# coqui-v1_0.net
KiCad netlist of a schematic drawn in EAGLE
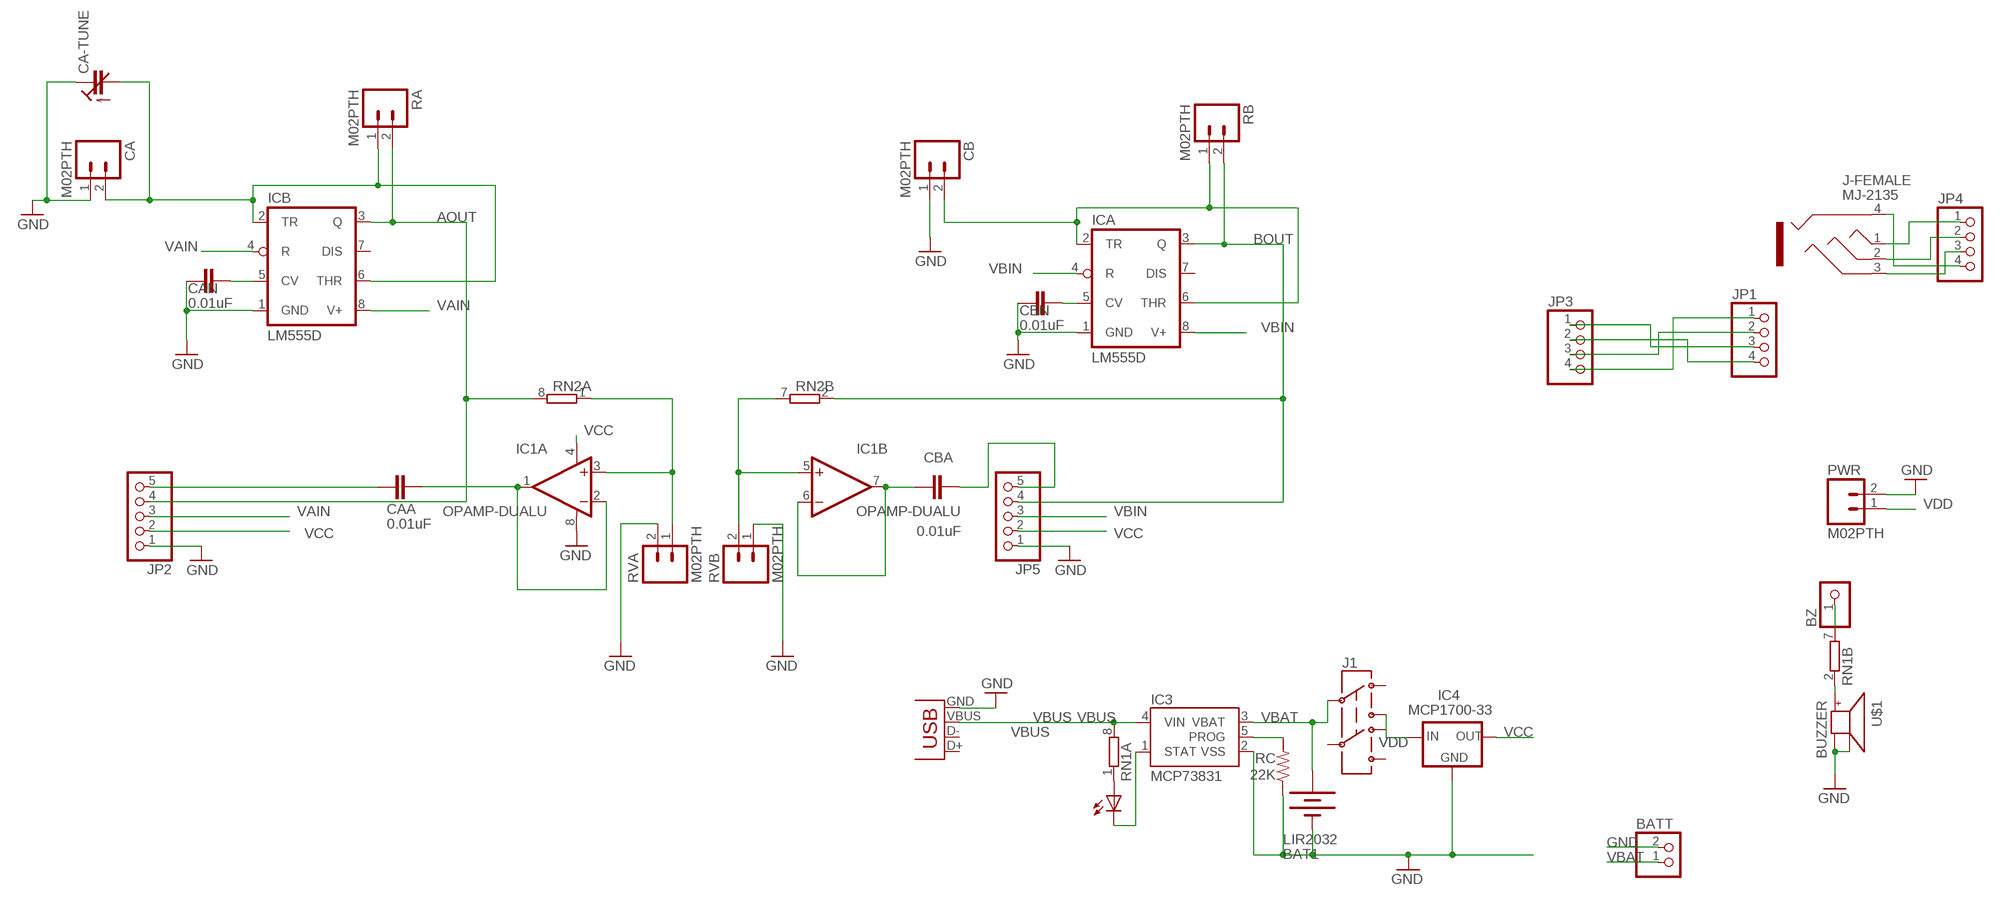
[diagram p0: schematic, sheet 1]

(export (version "E")
  (design (tool "Eeschema 10.0.6"))
  (components
    (comp (ref "BAT1")
      (value "LIR2032")
      (footprint "eagle-import:BATTCOM_20MM_PTH_SMT")
      (libsource (lib "eagle-import") (part "BATTERYBATTCOM_20MM_PTH_SMT"))
    )
    (comp (ref "BATT")
      (value "JST_2PIN-SMT-RA")
      (footprint "eagle-import:JST-PH-2-SMT-RA")
      (libsource (lib "eagle-import") (part "JST_2PIN-SMT-RA"))
    )
    (comp (ref "BZ")
      (value "PINHD-1X1")
      (footprint "eagle-import:1X01")
      (libsource (lib "eagle-import") (part "PINHD-1X1"))
    )
    (comp (ref "CA")
      (value "M02PTH")
      (footprint "eagle-import:1X02")
      (libsource (lib "eagle-import") (part "M02PTH"))
    )
    (comp (ref "CA-TUNE")
      (value "C-TRIMMTZBX4")
      (footprint "eagle-import:CTRIMTZBX4")
      (libsource (lib "eagle-import") (part "C-TRIMMTZBX4"))
    )
    (comp (ref "CAA")
      (value "0.01uF")
      (footprint "eagle-import:C0805@1")
      (libsource (lib "eagle-import") (part "C-EUC0805"))
    )
    (comp (ref "CAN")
      (value "0.01uF")
      (footprint "eagle-import:C0805@1")
      (libsource (lib "eagle-import") (part "C-EUC0805"))
    )
    (comp (ref "CB")
      (value "M02PTH")
      (footprint "eagle-import:1X02")
      (libsource (lib "eagle-import") (part "M02PTH"))
    )
    (comp (ref "CBA")
      (value "0.01uF")
      (footprint "eagle-import:C0805@1")
      (libsource (lib "eagle-import") (part "C-EUC0805"))
    )
    (comp (ref "CBN")
      (value "0.01uF")
      (footprint "eagle-import:C0805@1")
      (libsource (lib "eagle-import") (part "C-EUC0805"))
    )
    (comp (ref "CHG")
      (value "0805")
      (footprint "eagle-import:CHIPLED_0805")
      (libsource (lib "eagle-import") (part "LEDCHIPLED_0805"))
    )
    (comp (ref "IC1")
      (value "OPAMP-DUALU")
      (footprint "eagle-import:SO08")
      (libsource (lib "eagle-import") (part "OPAMP-DUALU"))
    )
    (comp (ref "IC3")
      (value "MCP73831")
      (footprint "eagle-import:SOT23-5")
      (libsource (lib "eagle-import") (part "MCP73831"))
    )
    (comp (ref "IC4")
      (value "MCP1700-33")
      (footprint "eagle-import:SOT89")
      (libsource (lib "eagle-import") (part "MCP1700SOT89"))
    )
    (comp (ref "ICA")
      (value "LM555D")
      (footprint "eagle-import:SO08")
      (libsource (lib "eagle-import") (part "555DLM"))
    )
    (comp (ref "ICB")
      (value "LM555D")
      (footprint "eagle-import:SO08")
      (libsource (lib "eagle-import") (part "555DLM"))
    )
    (comp (ref "J-FEMALE")
      (value "MJ-2135")
      (footprint "eagle-import:MJ-2135")
      (libsource (lib "eagle-import") (part "MJ-2135"))
    )
    (comp (ref "J1")
      (value "AYZ0202")
      (footprint "eagle-import:AYZ0202")
      (libsource (lib "eagle-import") (part "AYZ0202"))
    )
    (comp (ref "JP1")
      (value "PINHD-1X4/90")
      (footprint "eagle-import:1X04_90")
      (libsource (lib "eagle-import") (part "trrs-dwb_PINHD-1X4/90"))
    )
    (comp (ref "JP2")
      (value "PINHD-1X5")
      (footprint "eagle-import:1X05")
      (libsource (lib "eagle-import") (part "PINHD-1X5"))
    )
    (comp (ref "JP3")
      (value "PINHD-1X4")
      (footprint "eagle-import:1X04")
      (libsource (lib "eagle-import") (part "PINHD-1X4"))
    )
    (comp (ref "JP4")
      (value "PINHD-1X4")
      (footprint "eagle-import:1X04")
      (libsource (lib "eagle-import") (part "PINHD-1X4"))
    )
    (comp (ref "JP5")
      (value "PINHD-1X5")
      (footprint "eagle-import:1X05")
      (libsource (lib "eagle-import") (part "PINHD-1X5"))
    )
    (comp (ref "PWR")
      (value "M02PTH")
      (footprint "eagle-import:1X02")
      (libsource (lib "eagle-import") (part "M02PTH"))
    )
    (comp (ref "RA")
      (value "M02PTH")
      (footprint "eagle-import:1X02")
      (libsource (lib "eagle-import") (part "M02PTH"))
    )
    (comp (ref "RB")
      (value "M02PTH")
      (footprint "eagle-import:1X02")
      (libsource (lib "eagle-import") (part "M02PTH"))
    )
    (comp (ref "RC")
      (value "22K")
      (footprint "eagle-import:R0805")
      (libsource (lib "eagle-import") (part "R-US_R0805"))
    )
    (comp (ref "RN1")
      (value "4R-NEXB38V")
      (footprint "eagle-import:EXB38V")
      (libsource (lib "eagle-import") (part "4R-NEXB38V"))
    )
    (comp (ref "RN2")
      (value "4R-NEXB38V")
      (footprint "eagle-import:EXB38V")
      (libsource (lib "eagle-import") (part "4R-NEXB38V"))
    )
    (comp (ref "RVA")
      (value "M02PTH")
      (footprint "eagle-import:1X02")
      (libsource (lib "eagle-import") (part "M02PTH"))
    )
    (comp (ref "RVB")
      (value "M02PTH")
      (footprint "eagle-import:1X02")
      (libsource (lib "eagle-import") (part "M02PTH"))
    )
    (comp (ref "U$1")
      (value "BUZZER")
      (footprint "eagle-import:SMT-8585-BUZZER")
      (libsource (lib "eagle-import") (part "BUZZER"))
    )
    (comp (ref "X1")
      (value "USBSMD")
      (footprint "eagle-import:USB-MINIB")
      (libsource (lib "eagle-import") (part "USBSMD"))
    )
  )
  (nets
    (net (code "1") (name "/AOUT") (class "Default")
      (node (ref "ICB") (pin "3") (pinfunction "Q_3") (pintype "output"))
      (node (ref "JP2") (pin "4") (pinfunction "4_4") (pintype "passive"))
      (node (ref "RA") (pin "2") (pinfunction "2_2") (pintype "passive"))
      (node (ref "RN2") (pin "8") (pinfunction "2_8") (pintype "passive"))
    )
    (net (code "2") (name "/BOUT") (class "Default")
      (node (ref "ICA") (pin "3") (pinfunction "Q_3") (pintype "output"))
      (node (ref "JP5") (pin "4") (pinfunction "4_4") (pintype "passive"))
      (node (ref "RB") (pin "2") (pinfunction "2_2") (pintype "passive"))
      (node (ref "RN2") (pin "2") (pinfunction "1_2") (pintype "passive"))
    )
    (net (code "3") (name "/N$23") (class "Default")
      (node (ref "IC1") (pin "3") (pinfunction "+IN_3") (pintype "input"))
      (node (ref "IC1") (pin "5") (pinfunction "+IN_5") (pintype "input"))
      (node (ref "RN2") (pin "1") (pinfunction "1_1") (pintype "passive"))
      (node (ref "RN2") (pin "7") (pinfunction "2_7") (pintype "passive"))
      (node (ref "RVA") (pin "1") (pinfunction "1_1") (pintype "passive"))
      (node (ref "RVB") (pin "2") (pinfunction "2_2") (pintype "passive"))
    )
    (net (code "4") (name "/VAIN") (class "Default")
      (node (ref "ICB") (pin "4") (pinfunction "R_4") (pintype "input"))
      (node (ref "ICB") (pin "8") (pinfunction "V+_8") (pintype "power_in"))
      (node (ref "JP2") (pin "3") (pinfunction "3_3") (pintype "passive"))
    )
    (net (code "5") (name "/VBAT") (class "Default")
      (node (ref "BAT1") (pin "P$2") (pinfunction "+_P$2") (pintype "power_in"))
      (node (ref "BATT") (pin "1") (pinfunction "2_1") (pintype "passive"))
      (node (ref "IC3") (pin "3") (pinfunction "VBAT_3") (pintype "power_in"))
      (node (ref "J1") (pin "2") (pinfunction "2_2") (pintype "bidirectional"))
    )
    (net (code "6") (name "/VBIN") (class "Default")
      (node (ref "ICA") (pin "4") (pinfunction "R_4") (pintype "input"))
      (node (ref "ICA") (pin "8") (pinfunction "V+_8") (pintype "power_in"))
      (node (ref "JP5") (pin "3") (pinfunction "3_3") (pintype "passive"))
    )
    (net (code "7") (name "/VBUS") (class "Default")
      (node (ref "IC3") (pin "4") (pinfunction "VIN_4") (pintype "power_in"))
      (node (ref "RN1") (pin "8") (pinfunction "2_8") (pintype "passive"))
      (node (ref "X1") (pin "VBUS") (pinfunction "VBUS_VBUS") (pintype "bidirectional"))
    )
    (net (code "8") (name "/VCC") (class "Default")
      (node (ref "IC1") (pin "4") (pinfunction "V-_4") (pintype "power_in"))
      (node (ref "IC4") (pin "3") (pinfunction "OUT_3") (pintype "passive"))
      (node (ref "JP2") (pin "2") (pinfunction "2_2") (pintype "passive"))
      (node (ref "JP5") (pin "2") (pinfunction "2_2") (pintype "passive"))
    )
    (net (code "9") (name "/VDD") (class "Default")
      (node (ref "IC4") (pin "2") (pinfunction "IN_2") (pintype "input"))
      (node (ref "J1") (pin "1") (pinfunction "3_1") (pintype "bidirectional"))
      (node (ref "PWR") (pin "1") (pinfunction "1_1") (pintype "passive"))
    )
    (net (code "10") (name "GND") (class "Default")
      (node (ref "BAT1") (pin "P$1") (pinfunction "-_P$1") (pintype "power_in"))
      (node (ref "BATT") (pin "2") (pinfunction "1_2") (pintype "passive"))
      (node (ref "CA") (pin "1") (pinfunction "1_1") (pintype "passive"))
      (node (ref "CA-TUNE") (pin "1") (pinfunction "E_1") (pintype "passive"))
      (node (ref "CAN") (pin "1") (pinfunction "1_1") (pintype "passive"))
      (node (ref "CB") (pin "1") (pinfunction "1_1") (pintype "passive"))
      (node (ref "CBN") (pin "1") (pinfunction "1_1") (pintype "passive"))
      (node (ref "IC1") (pin "8") (pinfunction "V+_8") (pintype "power_in"))
      (node (ref "IC3") (pin "2") (pinfunction "VSS_2") (pintype "power_in"))
      (node (ref "IC4") (pin "1") (pinfunction "GND_1") (pintype "input"))
      (node (ref "ICA") (pin "1") (pinfunction "GND_1") (pintype "power_in"))
      (node (ref "ICB") (pin "1") (pinfunction "GND_1") (pintype "power_in"))
      (node (ref "JP2") (pin "1") (pinfunction "1_1") (pintype "passive"))
      (node (ref "JP5") (pin "1") (pinfunction "1_1") (pintype "passive"))
      (node (ref "PWR") (pin "2") (pinfunction "2_2") (pintype "passive"))
      (node (ref "RC") (pin "1") (pinfunction "1_1") (pintype "passive"))
      (node (ref "RVA") (pin "2") (pinfunction "2_2") (pintype "passive"))
      (node (ref "RVB") (pin "1") (pinfunction "1_1") (pintype "passive"))
      (node (ref "U$1") (pin "-") (pinfunction "-_-") (pintype "passive"))
      (node (ref "U$1") (pin "A-") (pinfunction "A-_A-") (pintype "passive"))
      (node (ref "X1") (pin "GND") (pinfunction "GND_GND") (pintype "bidirectional"))
    )
    (net (code "11") (name "Net-(CA-TUNE-A)") (class "Default")
      (node (ref "CA") (pin "2") (pinfunction "2_2") (pintype "passive"))
      (node (ref "CA-TUNE") (pin "2") (pinfunction "A_2") (pintype "passive"))
      (node (ref "ICB") (pin "2") (pinfunction "TR_2") (pintype "input"))
      (node (ref "ICB") (pin "6") (pinfunction "THR_6") (pintype "input"))
      (node (ref "RA") (pin "1") (pinfunction "1_1") (pintype "passive"))
    )
    (net (code "12") (name "Net-(CAA-Pad1)") (class "Default")
      (node (ref "CAA") (pin "1") (pinfunction "1_1") (pintype "passive"))
      (node (ref "JP2") (pin "5") (pinfunction "5_5") (pintype "passive"))
    )
    (net (code "13") (name "Net-(CBA-Pad2)") (class "Default")
      (node (ref "CBA") (pin "2") (pinfunction "2_2") (pintype "passive"))
      (node (ref "JP5") (pin "5") (pinfunction "5_5") (pintype "passive"))
    )
    (net (code "14") (name "Net-(CHG-PadA)") (class "Default")
      (node (ref "CHG") (pin "A") (pinfunction "A_A") (pintype "passive"))
      (node (ref "RN1") (pin "1") (pinfunction "1_1") (pintype "passive"))
    )
    (net (code "15") (name "Net-(IC1A--IN)") (class "Default")
      (node (ref "CAA") (pin "2") (pinfunction "2_2") (pintype "passive"))
      (node (ref "IC1") (pin "1") (pinfunction "OUT_1") (pintype "output"))
      (node (ref "IC1") (pin "2") (pinfunction "-IN_2") (pintype "input"))
    )
    (net (code "16") (name "Net-(IC1B--IN)") (class "Default")
      (node (ref "CBA") (pin "1") (pinfunction "1_1") (pintype "passive"))
      (node (ref "IC1") (pin "6") (pinfunction "-IN_6") (pintype "input"))
      (node (ref "IC1") (pin "7") (pinfunction "OUT_7") (pintype "output"))
    )
    (net (code "17") (name "Net-(IC3-PROG)") (class "Default")
      (node (ref "IC3") (pin "5") (pinfunction "PROG_5") (pintype "input"))
      (node (ref "RC") (pin "2") (pinfunction "2_2") (pintype "passive"))
    )
    (net (code "18") (name "Net-(IC3-STAT)") (class "Default")
      (node (ref "CHG") (pin "C") (pinfunction "C_C") (pintype "passive"))
      (node (ref "IC3") (pin "1") (pinfunction "STAT_1") (pintype "output"))
    )
    (net (code "19") (name "Net-(ICA-CV)") (class "Default")
      (node (ref "CBN") (pin "2") (pinfunction "2_2") (pintype "passive"))
      (node (ref "ICA") (pin "5") (pinfunction "CV_5") (pintype "input"))
    )
    (net (code "20") (name "Net-(ICA-THR)") (class "Default")
      (node (ref "CB") (pin "2") (pinfunction "2_2") (pintype "passive"))
      (node (ref "ICA") (pin "2") (pinfunction "TR_2") (pintype "input"))
      (node (ref "ICA") (pin "6") (pinfunction "THR_6") (pintype "input"))
      (node (ref "RB") (pin "1") (pinfunction "1_1") (pintype "passive"))
    )
    (net (code "21") (name "Net-(ICB-CV)") (class "Default")
      (node (ref "CAN") (pin "2") (pinfunction "2_2") (pintype "passive"))
      (node (ref "ICB") (pin "5") (pinfunction "CV_5") (pintype "input"))
    )
    (net (code "22") (name "Net-(J-FEMALE-Pad1)") (class "Default")
      (node (ref "J-FEMALE") (pin "1") (pinfunction "1_1") (pintype "passive"))
      (node (ref "JP4") (pin "1") (pinfunction "1_1") (pintype "passive"))
    )
    (net (code "23") (name "Net-(J-FEMALE-Pad2)") (class "Default")
      (node (ref "J-FEMALE") (pin "2") (pinfunction "2_2") (pintype "passive"))
      (node (ref "JP4") (pin "2") (pinfunction "2_2") (pintype "passive"))
    )
    (net (code "24") (name "Net-(J-FEMALE-Pad3)") (class "Default")
      (node (ref "J-FEMALE") (pin "3") (pinfunction "3_3") (pintype "passive"))
      (node (ref "JP4") (pin "3") (pinfunction "3_3") (pintype "passive"))
    )
    (net (code "25") (name "Net-(J-FEMALE-Pad4)") (class "Default")
      (node (ref "J-FEMALE") (pin "4") (pinfunction "4_4") (pintype "passive"))
      (node (ref "JP4") (pin "4") (pinfunction "4_4") (pintype "passive"))
    )
    (net (code "26") (name "Net-(JP1-Pad1)") (class "Default")
      (node (ref "JP1") (pin "1") (pinfunction "1_1") (pintype "passive"))
      (node (ref "JP3") (pin "4") (pinfunction "4_4") (pintype "passive"))
    )
    (net (code "27") (name "Net-(JP1-Pad2)") (class "Default")
      (node (ref "JP1") (pin "2") (pinfunction "2_2") (pintype "passive"))
      (node (ref "JP3") (pin "3") (pinfunction "3_3") (pintype "passive"))
    )
    (net (code "28") (name "Net-(JP1-Pad3)") (class "Default")
      (node (ref "JP1") (pin "3") (pinfunction "3_3") (pintype "passive"))
      (node (ref "JP3") (pin "1") (pinfunction "1_1") (pintype "passive"))
    )
    (net (code "29") (name "Net-(JP1-Pad4)") (class "Default")
      (node (ref "JP1") (pin "4") (pinfunction "4_4") (pintype "passive"))
      (node (ref "JP3") (pin "2") (pinfunction "2_2") (pintype "passive"))
    )
    (net (code "30") (name "Net-(RN1B-1)") (class "Default")
      (node (ref "RN1") (pin "2") (pinfunction "1_2") (pintype "passive"))
      (node (ref "U$1") (pin "+") (pinfunction "+_+") (pintype "passive"))
    )
    (net (code "31") (name "Net-(RN1B-2)") (class "Default")
      (node (ref "BZ") (pin "1") (pinfunction "1_1") (pintype "passive"))
      (node (ref "RN1") (pin "7") (pinfunction "2_7") (pintype "passive"))
    )
    (net (code "32") (name "unconnected-(ICA-DIS-Pad7)") (class "Default")
      (node (ref "ICA") (pin "7") (pinfunction "DIS_7") (pintype "input"))
    )
    (net (code "33") (name "unconnected-(ICB-DIS-Pad7)") (class "Default")
      (node (ref "ICB") (pin "7") (pinfunction "DIS_7") (pintype "input"))
    )
    (net (code "34") (name "unconnected-(J1-1-Pad3)") (class "Default")
      (node (ref "J1") (pin "3") (pinfunction "1_3") (pintype "bidirectional"))
    )
    (net (code "35") (name "unconnected-(J1-4-Pad6)") (class "Default")
      (node (ref "J1") (pin "6") (pinfunction "4_6") (pintype "bidirectional"))
    )
    (net (code "36") (name "unconnected-(J1-6-Pad4)") (class "Default")
      (node (ref "J1") (pin "4") (pinfunction "6_4") (pintype "bidirectional"))
    )
    (net (code "37") (name "unconnected-(J1-Pad5)") (class "Default")
      (node (ref "J1") (pin "5") (pinfunction "5_5") (pintype "bidirectional"))
    )
    (net (code "38") (name "unconnected-(X1-PadD+)") (class "Default")
      (node (ref "X1") (pin "D+") (pinfunction "D+_D+") (pintype "bidirectional"))
    )
    (net (code "39") (name "unconnected-(X1-PadD-)") (class "Default")
      (node (ref "X1") (pin "D-") (pinfunction "D-_D-") (pintype "bidirectional"))
    )
  )
)
